# knxhome.net
KiCad netlist of a schematic drawn in EAGLE
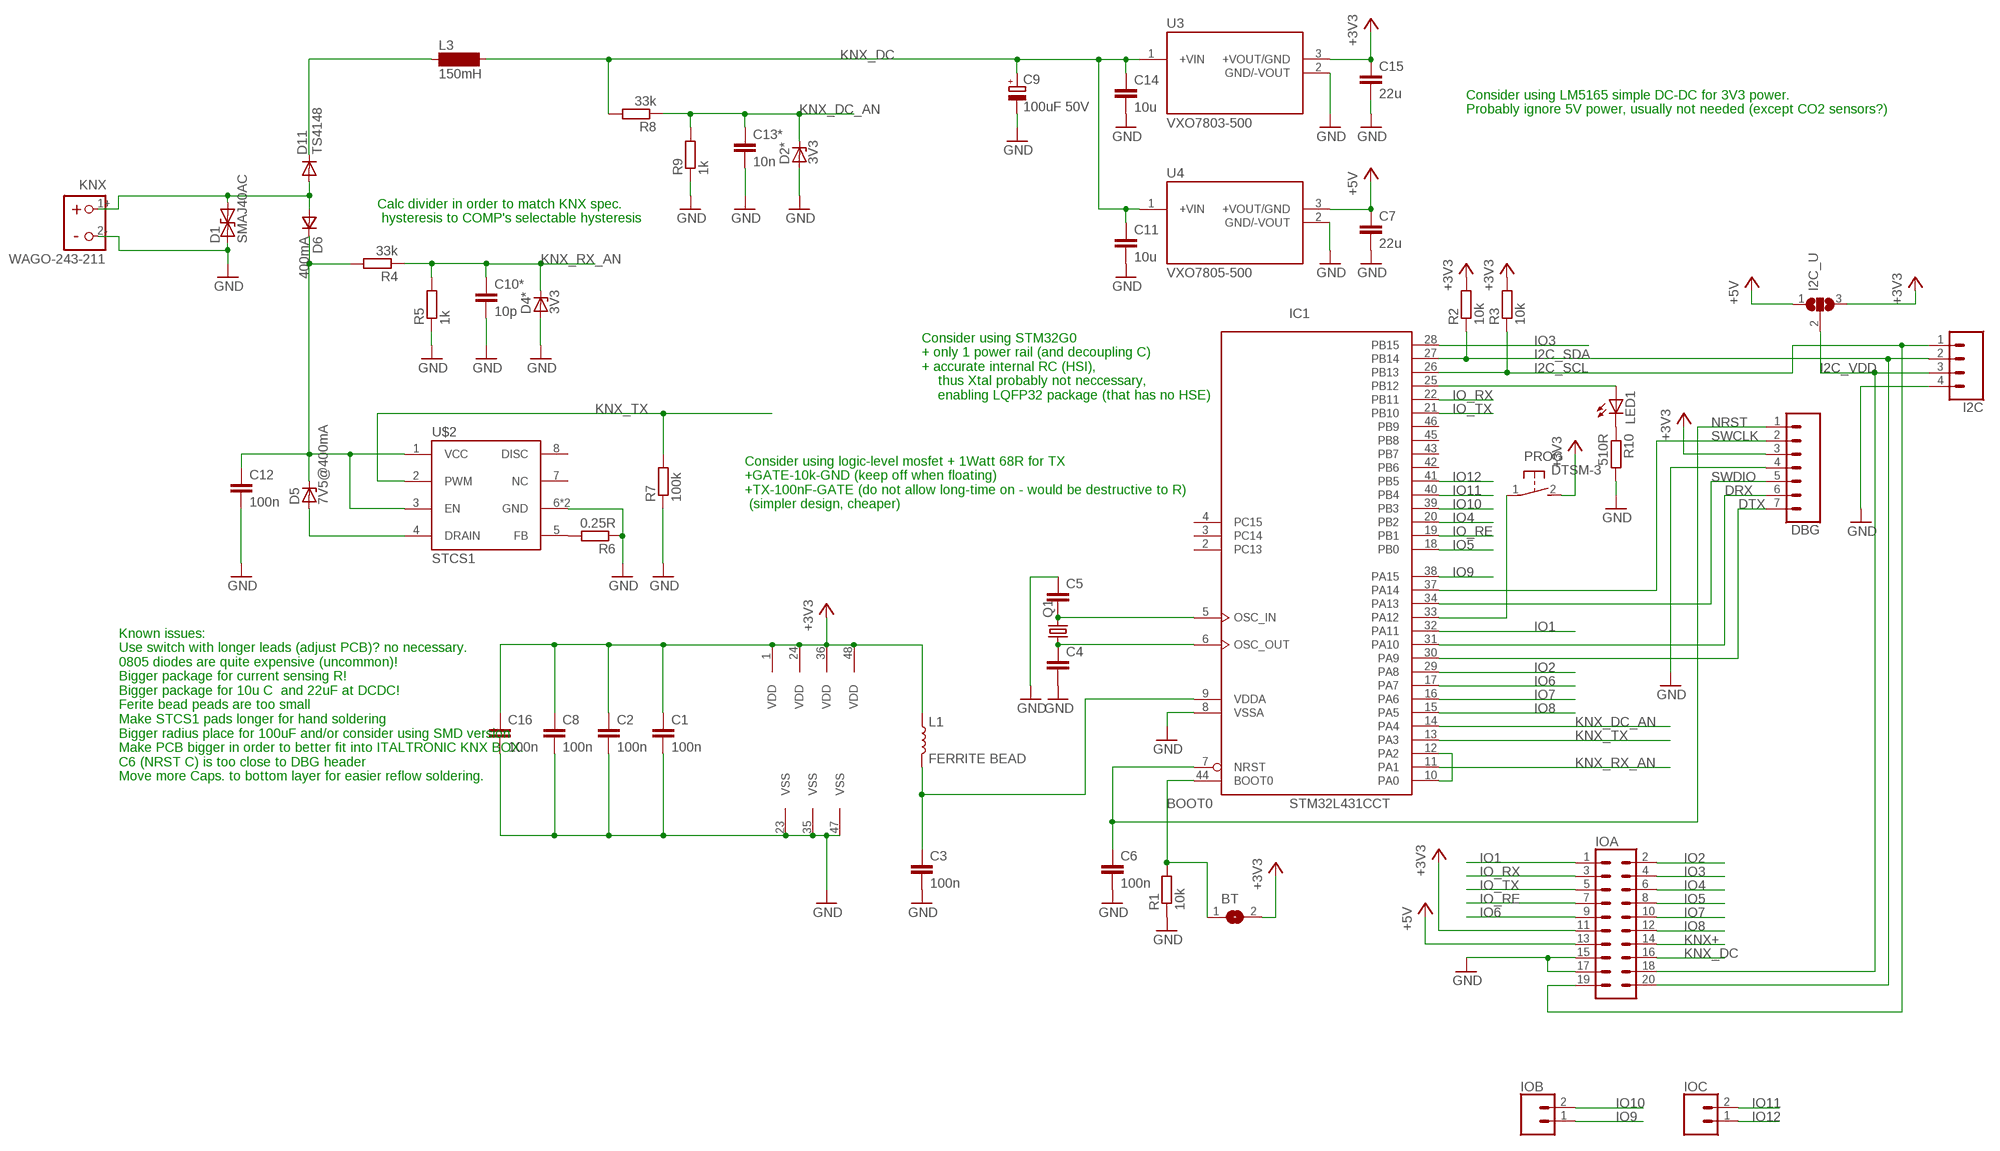
[diagram p0: schematic, sheet 1]

(export (version "E")
  (design (tool "Eeschema 10.0.6"))
  (components
    (comp (ref "BT") (value "SJ") (footprint "eagle-import:SJ") (libsource (lib "eagle-import") (part "SJ")))
    (comp (ref "C1")
      (value "100n")
      (footprint "eagle-import:C0805")
      (libsource (lib "eagle-import") (part "C-EUC0805"))
    )
    (comp (ref "C2")
      (value "100n")
      (footprint "eagle-import:C0805")
      (libsource (lib "eagle-import") (part "C-EUC0805"))
    )
    (comp (ref "C3")
      (value "100n")
      (footprint "eagle-import:C0805")
      (libsource (lib "eagle-import") (part "C-EUC0805"))
    )
    (comp (ref "C4")
      (value "C-EUC0805")
      (footprint "eagle-import:C0805")
      (libsource (lib "eagle-import") (part "C-EUC0805"))
    )
    (comp (ref "C5")
      (value "C-EUC0805")
      (footprint "eagle-import:C0805")
      (libsource (lib "eagle-import") (part "C-EUC0805"))
    )
    (comp (ref "C6")
      (value "100n")
      (footprint "eagle-import:C0805")
      (libsource (lib "eagle-import") (part "C-EUC0805"))
    )
    (comp (ref "C7")
      (value "22u")
      (footprint "eagle-import:C0805")
      (libsource (lib "eagle-import") (part "C-EUC0805"))
    )
    (comp (ref "C8")
      (value "100n")
      (footprint "eagle-import:C0805")
      (libsource (lib "eagle-import") (part "C-EUC0805"))
    )
    (comp (ref "C9")
      (value "100uF 50V")
      (footprint "eagle-import:E3,5-8")
      (libsource (lib "eagle-import") (part "CPOL-EUE3.5-8"))
    )
    (comp (ref "C10*")
      (value "10p")
      (footprint "eagle-import:C0805")
      (libsource (lib "eagle-import") (part "C-EUC0805"))
    )
    (comp (ref "C11")
      (value "10u")
      (footprint "eagle-import:C0805")
      (libsource (lib "eagle-import") (part "C-EUC0805"))
    )
    (comp (ref "C12")
      (value "100n")
      (footprint "eagle-import:C0805")
      (libsource (lib "eagle-import") (part "C-EUC0805"))
    )
    (comp (ref "C13*")
      (value "10n")
      (footprint "eagle-import:C0805")
      (libsource (lib "eagle-import") (part "C-EUC0805"))
    )
    (comp (ref "C14")
      (value "10u")
      (footprint "eagle-import:C0805")
      (libsource (lib "eagle-import") (part "C-EUC0805"))
    )
    (comp (ref "C15")
      (value "22u")
      (footprint "eagle-import:C0805")
      (libsource (lib "eagle-import") (part "C-EUC0805"))
    )
    (comp (ref "C16")
      (value "100n")
      (footprint "eagle-import:C0805")
      (libsource (lib "eagle-import") (part "C-EUC0805"))
    )
    (comp (ref "D1")
      (value "SMAJ40AC")
      (footprint "eagle-import:DO-214AC")
      (libsource (lib "eagle-import") (part "SMAJ40AC"))
    )
    (comp (ref "D2*")
      (value "3V3")
      (footprint "eagle-import:SOT23")
      (libsource (lib "eagle-import") (part "ZENER-DIODESOT23"))
    )
    (comp (ref "D4*")
      (value "3V3")
      (footprint "eagle-import:SOT23")
      (libsource (lib "eagle-import") (part "ZENER-DIODESOT23"))
    )
    (comp (ref "D5")
      (value "7V5@400mA")
      (footprint "eagle-import:SMB")
      (libsource (lib "eagle-import") (part "diode_210_ZENER-DIODESMB"))
    )
    (comp (ref "D6")
      (value "400mA")
      (footprint "eagle-import:SOD323")
      (fields (field (name "MPN") "CDSOD323-T05C"))
      (libsource (lib "eagle-import") (part "DSOD323"))
    )
    (comp (ref "D11")
      (value "TS4148")
      (footprint "eagle-import:D0805")
      (libsource (lib "eagle-import") (part "DIODE-D0805"))
    )
    (comp (ref "DBG")
      (value "CONN_07LOCK")
      (footprint "eagle-import:1X07_LOCK")
      (libsource (lib "eagle-import") (part "CONN_07LOCK"))
    )
    (comp (ref "I2C")
      (value "CONN_04JST-PTH-VERT")
      (footprint "eagle-import:JST-4-PTH-VERT")
      (libsource (lib "eagle-import") (part "CONN_04JST-PTH-VERT"))
    )
    (comp (ref "I2C_U")
      (value "SJ2W")
      (footprint "eagle-import:SJ_2")
      (libsource (lib "eagle-import") (part "SJ2W"))
    )
    (comp (ref "IC1")
      (value "STM32L431CCT")
      (footprint "eagle-import:LQFP48")
      (libsource (lib "eagle-import") (part "STM32L051CT8"))
    )
    (comp (ref "IOA")
      (value "CONN_10X2")
      (footprint "eagle-import:2X10")
      (libsource (lib "eagle-import") (part "CONN_10X2"))
    )
    (comp (ref "IOB")
      (value "CONN_02")
      (footprint "eagle-import:1X02")
      (libsource (lib "eagle-import") (part "CONN_02"))
    )
    (comp (ref "IOC")
      (value "CONN_02")
      (footprint "eagle-import:1X02")
      (libsource (lib "eagle-import") (part "CONN_02"))
    )
    (comp (ref "KNX")
      (value "WAGO-243-211")
      (footprint "eagle-import:WAGO-243-211")
      (libsource (lib "eagle-import") (part "WAGO-243-211"))
    )
    (comp (ref "L1")
      (value "FERRITE BEAD")
      (footprint "eagle-import:0805")
      (libsource (lib "eagle-import") (part "INDUCTOR-0805-3.3UH"))
    )
    (comp (ref "L3")
      (value "150mH")
      (footprint "eagle-import:BS11_LIEGEND")
      (libsource (lib "eagle-import") (part "SD12BS11_LIEGEND"))
    )
    (comp (ref "LED1")
      (value "LED3MM")
      (footprint "eagle-import:LED3MM")
      (libsource (lib "eagle-import") (part "LED3MM"))
    )
    (comp (ref "PROG")
      (value "DTSM-3")
      (footprint "eagle-import:DTSM-3")
      (libsource (lib "eagle-import") (part "DTSM-3"))
    )
    (comp (ref "Q1")
      (value "CRYSTALHC49S")
      (footprint "eagle-import:HC49_S")
      (libsource (lib "eagle-import") (part "CRYSTALHC49S"))
    )
    (comp (ref "R1")
      (value "10k")
      (footprint "eagle-import:R0805")
      (libsource (lib "eagle-import") (part "R-EU_R0805"))
    )
    (comp (ref "R2")
      (value "10k")
      (footprint "eagle-import:R0805")
      (libsource (lib "eagle-import") (part "R-EU_R0805"))
    )
    (comp (ref "R3")
      (value "10k")
      (footprint "eagle-import:R0805")
      (libsource (lib "eagle-import") (part "R-EU_R0805"))
    )
    (comp (ref "R4")
      (value "33k")
      (footprint "eagle-import:R0805")
      (libsource (lib "eagle-import") (part "R-EU_R0805"))
    )
    (comp (ref "R5")
      (value "1k")
      (footprint "eagle-import:R0805")
      (libsource (lib "eagle-import") (part "R-EU_R0805"))
    )
    (comp (ref "R6")
      (value "0.25R")
      (footprint "eagle-import:R0805")
      (libsource (lib "eagle-import") (part "R-EU_R0805"))
    )
    (comp (ref "R7")
      (value "100k")
      (footprint "eagle-import:R0805")
      (libsource (lib "eagle-import") (part "R-EU_R0805"))
    )
    (comp (ref "R8")
      (value "33k")
      (footprint "eagle-import:R0805")
      (libsource (lib "eagle-import") (part "R-EU_R0805"))
    )
    (comp (ref "R9")
      (value "1k")
      (footprint "eagle-import:R0805")
      (libsource (lib "eagle-import") (part "R-EU_R0805"))
    )
    (comp (ref "R10")
      (value "510R")
      (footprint "eagle-import:R0805")
      (libsource (lib "eagle-import") (part "R-EU_R0805"))
    )
    (comp (ref "U$2")
      (value "STCS1")
      (footprint "eagle-import:POWERSO-8")
      (libsource (lib "eagle-import") (part "STCS1"))
    )
    (comp (ref "U3")
      (value "VXO7803-500")
      (footprint "eagle-import:CONV_VXO7803-500")
      (fields (field (name "MANUFACTURER") "CUI Inc"))
      (libsource (lib "eagle-import") (part "VXO7803-500"))
    )
    (comp (ref "U4")
      (value "VXO7805-500")
      (footprint "eagle-import:CONV_VXO7803-500")
      (fields (field (name "MANUFACTURER") "CUI Inc"))
      (libsource (lib "eagle-import") (part "VXO7803-500"))
    )
  )
  (nets
    (net (code "1") (name "+3V3") (class "Default")
      (node (ref "BT") (pin "2") (pinfunction "2_2") (pintype "passive"))
      (node (ref "C1") (pin "1") (pinfunction "1_1") (pintype "passive"))
      (node (ref "C15") (pin "1") (pinfunction "1_1") (pintype "passive"))
      (node (ref "C16") (pin "1") (pinfunction "1_1") (pintype "passive"))
      (node (ref "C2") (pin "1") (pinfunction "1_1") (pintype "passive"))
      (node (ref "C8") (pin "1") (pinfunction "1_1") (pintype "passive"))
      (node (ref "DBG") (pin "3") (pinfunction "3_3") (pintype "passive"))
      (node (ref "I2C_U") (pin "3") (pinfunction "3_3") (pintype "passive"))
      (node (ref "IC1") (pin "1") (pinfunction "VDD_1") (pintype "power_in"))
      (node (ref "IC1") (pin "24") (pinfunction "VDD_24") (pintype "power_in"))
      (node (ref "IC1") (pin "36") (pinfunction "VDD_36") (pintype "power_in"))
      (node (ref "IC1") (pin "48") (pinfunction "VDD_48") (pintype "power_in"))
      (node (ref "IOA") (pin "11") (pinfunction "11_11") (pintype "passive"))
      (node (ref "L1") (pin "1") (pinfunction "1_1") (pintype "passive"))
      (node (ref "PROG") (pin "2") (pinfunction "2_2") (pintype "passive"))
      (node (ref "R2") (pin "2") (pinfunction "2_2") (pintype "passive"))
      (node (ref "R3") (pin "2") (pinfunction "2_2") (pintype "passive"))
      (node (ref "U3") (pin "3") (pinfunction "+VOUT/GND_3") (pintype "output"))
    )
    (net (code "2") (name "+5V") (class "Default")
      (node (ref "C7") (pin "1") (pinfunction "1_1") (pintype "passive"))
      (node (ref "I2C_U") (pin "1") (pinfunction "1_1") (pintype "passive"))
      (node (ref "IOA") (pin "13") (pinfunction "13_13") (pintype "passive"))
      (node (ref "U4") (pin "3") (pinfunction "+VOUT/GND_3") (pintype "output"))
    )
    (net (code "3") (name "/BOOT0") (class "Default")
      (node (ref "BT") (pin "1") (pinfunction "1_1") (pintype "passive"))
      (node (ref "IC1") (pin "44") (pinfunction "BOOT0_44") (pintype "input"))
      (node (ref "R1") (pin "2") (pinfunction "2_2") (pintype "passive"))
    )
    (net (code "4") (name "/DRX") (class "Default")
      (node (ref "DBG") (pin "6") (pinfunction "6_6") (pintype "passive"))
      (node (ref "IC1") (pin "31") (pinfunction "PA10_31") (pintype "bidirectional"))
    )
    (net (code "5") (name "/DTX") (class "Default")
      (node (ref "DBG") (pin "7") (pinfunction "7_7") (pintype "passive"))
      (node (ref "IC1") (pin "30") (pinfunction "PA9_30") (pintype "bidirectional"))
    )
    (net (code "6") (name "/I2C_SCL") (class "Default")
      (node (ref "I2C") (pin "1") (pinfunction "1_1") (pintype "passive"))
      (node (ref "IC1") (pin "26") (pinfunction "PB13_26") (pintype "bidirectional"))
      (node (ref "IOA") (pin "19") (pinfunction "19_19") (pintype "passive"))
      (node (ref "R3") (pin "1") (pinfunction "1_1") (pintype "passive"))
    )
    (net (code "7") (name "/I2C_SDA") (class "Default")
      (node (ref "I2C") (pin "2") (pinfunction "2_2") (pintype "passive"))
      (node (ref "IC1") (pin "27") (pinfunction "PB14_27") (pintype "bidirectional"))
      (node (ref "IOA") (pin "20") (pinfunction "20_20") (pintype "passive"))
      (node (ref "R2") (pin "1") (pinfunction "1_1") (pintype "passive"))
    )
    (net (code "8") (name "/I2C_VDD") (class "Default")
      (node (ref "I2C") (pin "3") (pinfunction "3_3") (pintype "passive"))
      (node (ref "I2C_U") (pin "2") (pinfunction "2_2") (pintype "passive"))
      (node (ref "IOA") (pin "18") (pinfunction "18_18") (pintype "passive"))
    )
    (net (code "9") (name "/IO1") (class "Default")
      (node (ref "IC1") (pin "32") (pinfunction "PA11_32") (pintype "bidirectional"))
      (node (ref "IOA") (pin "1") (pinfunction "1_1") (pintype "passive"))
    )
    (net (code "10") (name "/IO2") (class "Default")
      (node (ref "IC1") (pin "29") (pinfunction "PA8_29") (pintype "bidirectional"))
      (node (ref "IOA") (pin "2") (pinfunction "2_2") (pintype "passive"))
    )
    (net (code "11") (name "/IO3") (class "Default")
      (node (ref "IC1") (pin "28") (pinfunction "PB15_28") (pintype "bidirectional"))
      (node (ref "IOA") (pin "4") (pinfunction "4_4") (pintype "passive"))
    )
    (net (code "12") (name "/IO4") (class "Default")
      (node (ref "IC1") (pin "20") (pinfunction "PB2_20") (pintype "bidirectional"))
      (node (ref "IOA") (pin "6") (pinfunction "6_6") (pintype "passive"))
    )
    (net (code "13") (name "/IO5") (class "Default")
      (node (ref "IC1") (pin "18") (pinfunction "PB0_18") (pintype "bidirectional"))
      (node (ref "IOA") (pin "8") (pinfunction "8_8") (pintype "passive"))
    )
    (net (code "14") (name "/IO6") (class "Default")
      (node (ref "IC1") (pin "17") (pinfunction "PA7_17") (pintype "bidirectional"))
      (node (ref "IOA") (pin "9") (pinfunction "9_9") (pintype "passive"))
    )
    (net (code "15") (name "/IO7") (class "Default")
      (node (ref "IC1") (pin "16") (pinfunction "PA6_16") (pintype "bidirectional"))
      (node (ref "IOA") (pin "10") (pinfunction "10_10") (pintype "passive"))
    )
    (net (code "16") (name "/IO8") (class "Default")
      (node (ref "IC1") (pin "15") (pinfunction "PA5_15") (pintype "bidirectional"))
      (node (ref "IOA") (pin "12") (pinfunction "12_12") (pintype "passive"))
    )
    (net (code "17") (name "/IO9") (class "Default")
      (node (ref "IC1") (pin "38") (pinfunction "PA15_38") (pintype "bidirectional"))
      (node (ref "IOB") (pin "1") (pinfunction "1_1") (pintype "passive"))
    )
    (net (code "18") (name "/IO10") (class "Default")
      (node (ref "IC1") (pin "39") (pinfunction "PB3_39") (pintype "bidirectional"))
      (node (ref "IOB") (pin "2") (pinfunction "2_2") (pintype "passive"))
    )
    (net (code "19") (name "/IO11") (class "Default")
      (node (ref "IC1") (pin "40") (pinfunction "PB4_40") (pintype "bidirectional"))
      (node (ref "IOC") (pin "2") (pinfunction "2_2") (pintype "passive"))
    )
    (net (code "20") (name "/IO12") (class "Default")
      (node (ref "IC1") (pin "41") (pinfunction "PB5_41") (pintype "bidirectional"))
      (node (ref "IOC") (pin "1") (pinfunction "1_1") (pintype "passive"))
    )
    (net (code "21") (name "/IO_RE") (class "Default")
      (node (ref "IC1") (pin "19") (pinfunction "PB1_19") (pintype "bidirectional"))
      (node (ref "IOA") (pin "7") (pinfunction "7_7") (pintype "passive"))
    )
    (net (code "22") (name "/IO_RX") (class "Default")
      (node (ref "IC1") (pin "22") (pinfunction "PB11_22") (pintype "bidirectional"))
      (node (ref "IOA") (pin "3") (pinfunction "3_3") (pintype "passive"))
    )
    (net (code "23") (name "/IO_TX") (class "Default")
      (node (ref "IC1") (pin "21") (pinfunction "PB10_21") (pintype "bidirectional"))
      (node (ref "IOA") (pin "5") (pinfunction "5_5") (pintype "passive"))
    )
    (net (code "24") (name "/KNX+") (class "Default")
      (node (ref "D1") (pin "C") (pinfunction "C_C") (pintype "passive"))
      (node (ref "D11") (pin "A") (pinfunction "A_A") (pintype "passive"))
      (node (ref "D6") (pin "2") (pinfunction "A_2") (pintype "passive"))
      (node (ref "IOA") (pin "14") (pinfunction "14_14") (pintype "passive"))
      (node (ref "KNX") (pin "1+") (pinfunction "1+_1+") (pintype "passive"))
    )
    (net (code "25") (name "/KNX_DC") (class "Default")
      (node (ref "C11") (pin "1") (pinfunction "1_1") (pintype "passive"))
      (node (ref "C14") (pin "1") (pinfunction "1_1") (pintype "passive"))
      (node (ref "C9") (pin "+") (pinfunction "+_+") (pintype "passive"))
      (node (ref "IOA") (pin "16") (pinfunction "16_16") (pintype "passive"))
      (node (ref "L3") (pin "2") (pinfunction "2_2") (pintype "passive"))
      (node (ref "R8") (pin "2") (pinfunction "2_2") (pintype "passive"))
      (node (ref "U3") (pin "1") (pinfunction "+VIN_1") (pintype "input"))
      (node (ref "U4") (pin "1") (pinfunction "+VIN_1") (pintype "input"))
    )
    (net (code "26") (name "/KNX_DC_AN") (class "Default")
      (node (ref "C13*") (pin "1") (pinfunction "1_1") (pintype "passive"))
      (node (ref "D2*") (pin "3") (pinfunction "C_3") (pintype "passive"))
      (node (ref "IC1") (pin "14") (pinfunction "PA4_14") (pintype "bidirectional"))
      (node (ref "R8") (pin "1") (pinfunction "1_1") (pintype "passive"))
      (node (ref "R9") (pin "2") (pinfunction "2_2") (pintype "passive"))
    )
    (net (code "27") (name "/KNX_RX_AN") (class "Default")
      (node (ref "C10*") (pin "1") (pinfunction "1_1") (pintype "passive"))
      (node (ref "D4*") (pin "3") (pinfunction "C_3") (pintype "passive"))
      (node (ref "IC1") (pin "11") (pinfunction "PA1_11") (pintype "bidirectional"))
      (node (ref "R4") (pin "1") (pinfunction "1_1") (pintype "passive"))
      (node (ref "R5") (pin "2") (pinfunction "2_2") (pintype "passive"))
    )
    (net (code "28") (name "/KNX_TX") (class "Default")
      (node (ref "IC1") (pin "13") (pinfunction "PA3_13") (pintype "bidirectional"))
      (node (ref "R7") (pin "2") (pinfunction "2_2") (pintype "passive"))
      (node (ref "U$2") (pin "2") (pinfunction "PWM_2") (pintype "bidirectional"))
    )
    (net (code "29") (name "/NRST") (class "Default")
      (node (ref "C6") (pin "1") (pinfunction "1_1") (pintype "passive"))
      (node (ref "DBG") (pin "1") (pinfunction "1_1") (pintype "passive"))
      (node (ref "IC1") (pin "7") (pinfunction "NRST_7") (pintype "bidirectional"))
    )
    (net (code "30") (name "/SWCLK") (class "Default")
      (node (ref "DBG") (pin "2") (pinfunction "2_2") (pintype "passive"))
      (node (ref "IC1") (pin "37") (pinfunction "PA14_37") (pintype "bidirectional"))
    )
    (net (code "31") (name "/SWDIO") (class "Default")
      (node (ref "DBG") (pin "5") (pinfunction "5_5") (pintype "passive"))
      (node (ref "IC1") (pin "34") (pinfunction "PA13_34") (pintype "bidirectional"))
    )
    (net (code "32") (name "GND") (class "Default")
      (node (ref "C1") (pin "2") (pinfunction "2_2") (pintype "passive"))
      (node (ref "C10*") (pin "2") (pinfunction "2_2") (pintype "passive"))
      (node (ref "C11") (pin "2") (pinfunction "2_2") (pintype "passive"))
      (node (ref "C12") (pin "2") (pinfunction "2_2") (pintype "passive"))
      (node (ref "C13*") (pin "2") (pinfunction "2_2") (pintype "passive"))
      (node (ref "C14") (pin "2") (pinfunction "2_2") (pintype "passive"))
      (node (ref "C15") (pin "2") (pinfunction "2_2") (pintype "passive"))
      (node (ref "C16") (pin "2") (pinfunction "2_2") (pintype "passive"))
      (node (ref "C2") (pin "2") (pinfunction "2_2") (pintype "passive"))
      (node (ref "C3") (pin "2") (pinfunction "2_2") (pintype "passive"))
      (node (ref "C4") (pin "2") (pinfunction "2_2") (pintype "passive"))
      (node (ref "C5") (pin "1") (pinfunction "1_1") (pintype "passive"))
      (node (ref "C6") (pin "2") (pinfunction "2_2") (pintype "passive"))
      (node (ref "C7") (pin "2") (pinfunction "2_2") (pintype "passive"))
      (node (ref "C8") (pin "2") (pinfunction "2_2") (pintype "passive"))
      (node (ref "C9") (pin "-") (pinfunction "-_-") (pintype "passive"))
      (node (ref "D1") (pin "A") (pinfunction "A_A") (pintype "passive"))
      (node (ref "D2*") (pin "1") (pinfunction "A_1") (pintype "passive"))
      (node (ref "D4*") (pin "1") (pinfunction "A_1") (pintype "passive"))
      (node (ref "DBG") (pin "4") (pinfunction "4_4") (pintype "passive"))
      (node (ref "I2C") (pin "4") (pinfunction "4_4") (pintype "passive"))
      (node (ref "IC1") (pin "23") (pinfunction "VSS_23") (pintype "power_in"))
      (node (ref "IC1") (pin "35") (pinfunction "VSS_35") (pintype "power_in"))
      (node (ref "IC1") (pin "47") (pinfunction "VSS_47") (pintype "power_in"))
      (node (ref "IC1") (pin "8") (pinfunction "VSSA_8") (pintype "power_in"))
      (node (ref "IOA") (pin "15") (pinfunction "15_15") (pintype "passive"))
      (node (ref "IOA") (pin "17") (pinfunction "17_17") (pintype "passive"))
      (node (ref "KNX") (pin "2-") (pinfunction "2-_2-") (pintype "passive"))
      (node (ref "R1") (pin "1") (pinfunction "1_1") (pintype "passive"))
      (node (ref "R10") (pin "2") (pinfunction "2_2") (pintype "passive"))
      (node (ref "R5") (pin "1") (pinfunction "1_1") (pintype "passive"))
      (node (ref "R6") (pin "1") (pinfunction "1_1") (pintype "passive"))
      (node (ref "R7") (pin "1") (pinfunction "1_1") (pintype "passive"))
      (node (ref "R9") (pin "1") (pinfunction "1_1") (pintype "passive"))
      (node (ref "U$2") (pin "6") (pinfunction "GND_6") (pintype "bidirectional"))
      (node (ref "U$2") (pin "EX") (pinfunction "GND_EX") (pintype "bidirectional"))
      (node (ref "U3") (pin "2") (pinfunction "GND/-VOUT_2") (pintype "output"))
      (node (ref "U4") (pin "2") (pinfunction "GND/-VOUT_2") (pintype "output"))
    )
    (net (code "33") (name "Net-(D6-C)") (class "Default")
      (node (ref "C12") (pin "1") (pinfunction "1_1") (pintype "passive"))
      (node (ref "D5") (pin "C") (pinfunction "C_C") (pintype "passive"))
      (node (ref "D6") (pin "1") (pinfunction "C_1") (pintype "passive"))
      (node (ref "R4") (pin "2") (pinfunction "2_2") (pintype "passive"))
      (node (ref "U$2") (pin "1") (pinfunction "VCC_1") (pintype "power_in"))
      (node (ref "U$2") (pin "3") (pinfunction "EN_3") (pintype "bidirectional"))
    )
    (net (code "34") (name "Net-(D11-PadC)") (class "Default")
      (node (ref "D11") (pin "C") (pinfunction "C_C") (pintype "passive"))
      (node (ref "L3") (pin "1") (pinfunction "1_1") (pintype "passive"))
    )
    (net (code "35") (name "Net-(IC1A-OSC_IN)") (class "Default")
      (node (ref "C5") (pin "2") (pinfunction "2_2") (pintype "passive"))
      (node (ref "IC1") (pin "5") (pinfunction "OSC_IN_5") (pintype "bidirectional"))
      (node (ref "Q1") (pin "2") (pinfunction "2_2") (pintype "passive"))
    )
    (net (code "36") (name "Net-(IC1A-OSC_OUT)") (class "Default")
      (node (ref "C4") (pin "1") (pinfunction "1_1") (pintype "passive"))
      (node (ref "IC1") (pin "6") (pinfunction "OSC_OUT_6") (pintype "bidirectional"))
      (node (ref "Q1") (pin "1") (pinfunction "1_1") (pintype "passive"))
    )
    (net (code "37") (name "Net-(IC1A-PA0)") (class "Default")
      (node (ref "IC1") (pin "10") (pinfunction "PA0_10") (pintype "bidirectional"))
      (node (ref "IC1") (pin "12") (pinfunction "PA2_12") (pintype "bidirectional"))
    )
    (net (code "38") (name "Net-(IC1A-PA12)") (class "Default")
      (node (ref "IC1") (pin "33") (pinfunction "PA12_33") (pintype "bidirectional"))
      (node (ref "PROG") (pin "1") (pinfunction "1_1") (pintype "passive"))
    )
    (net (code "39") (name "Net-(IC1A-PB12)") (class "Default")
      (node (ref "IC1") (pin "25") (pinfunction "PB12_25") (pintype "bidirectional"))
      (node (ref "LED1") (pin "A") (pinfunction "A_A") (pintype "passive"))
    )
    (net (code "40") (name "Net-(IC1A-VDDA)") (class "Default")
      (node (ref "C3") (pin "1") (pinfunction "1_1") (pintype "passive"))
      (node (ref "IC1") (pin "9") (pinfunction "VDDA_9") (pintype "power_in"))
      (node (ref "L1") (pin "2") (pinfunction "2_2") (pintype "passive"))
    )
    (net (code "41") (name "Net-(LED1-C)") (class "Default")
      (node (ref "LED1") (pin "K") (pinfunction "C_K") (pintype "passive"))
      (node (ref "R10") (pin "1") (pinfunction "1_1") (pintype "passive"))
    )
    (net (code "42") (name "Net-(U$2-DRAIN)") (class "Default")
      (node (ref "D5") (pin "A") (pinfunction "A_A") (pintype "passive"))
      (node (ref "U$2") (pin "4") (pinfunction "DRAIN_4") (pintype "bidirectional"))
    )
    (net (code "43") (name "Net-(U$2-FB)") (class "Default")
      (node (ref "R6") (pin "2") (pinfunction "2_2") (pintype "passive"))
      (node (ref "U$2") (pin "5") (pinfunction "FB_5") (pintype "bidirectional"))
    )
    (net (code "44") (name "unconnected-(IC1A-PB6-Pad42)") (class "Default")
      (node (ref "IC1") (pin "42") (pinfunction "PB6_42") (pintype "bidirectional"))
    )
    (net (code "45") (name "unconnected-(IC1A-PB7-Pad43)") (class "Default")
      (node (ref "IC1") (pin "43") (pinfunction "PB7_43") (pintype "bidirectional"))
    )
    (net (code "46") (name "unconnected-(IC1A-PB8-Pad45)") (class "Default")
      (node (ref "IC1") (pin "45") (pinfunction "PB8_45") (pintype "bidirectional"))
    )
    (net (code "47") (name "unconnected-(IC1A-PB9-Pad46)") (class "Default")
      (node (ref "IC1") (pin "46") (pinfunction "PB9_46") (pintype "bidirectional"))
    )
    (net (code "48") (name "unconnected-(IC1A-PC13-Pad2)") (class "Default")
      (node (ref "IC1") (pin "2") (pinfunction "PC13_2") (pintype "bidirectional"))
    )
    (net (code "49") (name "unconnected-(IC1A-PC14-Pad3)") (class "Default")
      (node (ref "IC1") (pin "3") (pinfunction "PC14_3") (pintype "bidirectional"))
    )
    (net (code "50") (name "unconnected-(IC1A-PC15-Pad4)") (class "Default")
      (node (ref "IC1") (pin "4") (pinfunction "PC15_4") (pintype "bidirectional"))
    )
    (net (code "51") (name "unconnected-(U$2-DISC-Pad8)") (class "Default")
      (node (ref "U$2") (pin "8") (pinfunction "DISC_8") (pintype "bidirectional"))
    )
    (net (code "52") (name "unconnected-(U$2-NC-Pad7)") (class "Default")
      (node (ref "U$2") (pin "7") (pinfunction "NC_7") (pintype "no_connect"))
    )
  )
)
